# TG21_Slave_Device_Led.net
KiCad netlist of a schematic drawn in Altium Designer
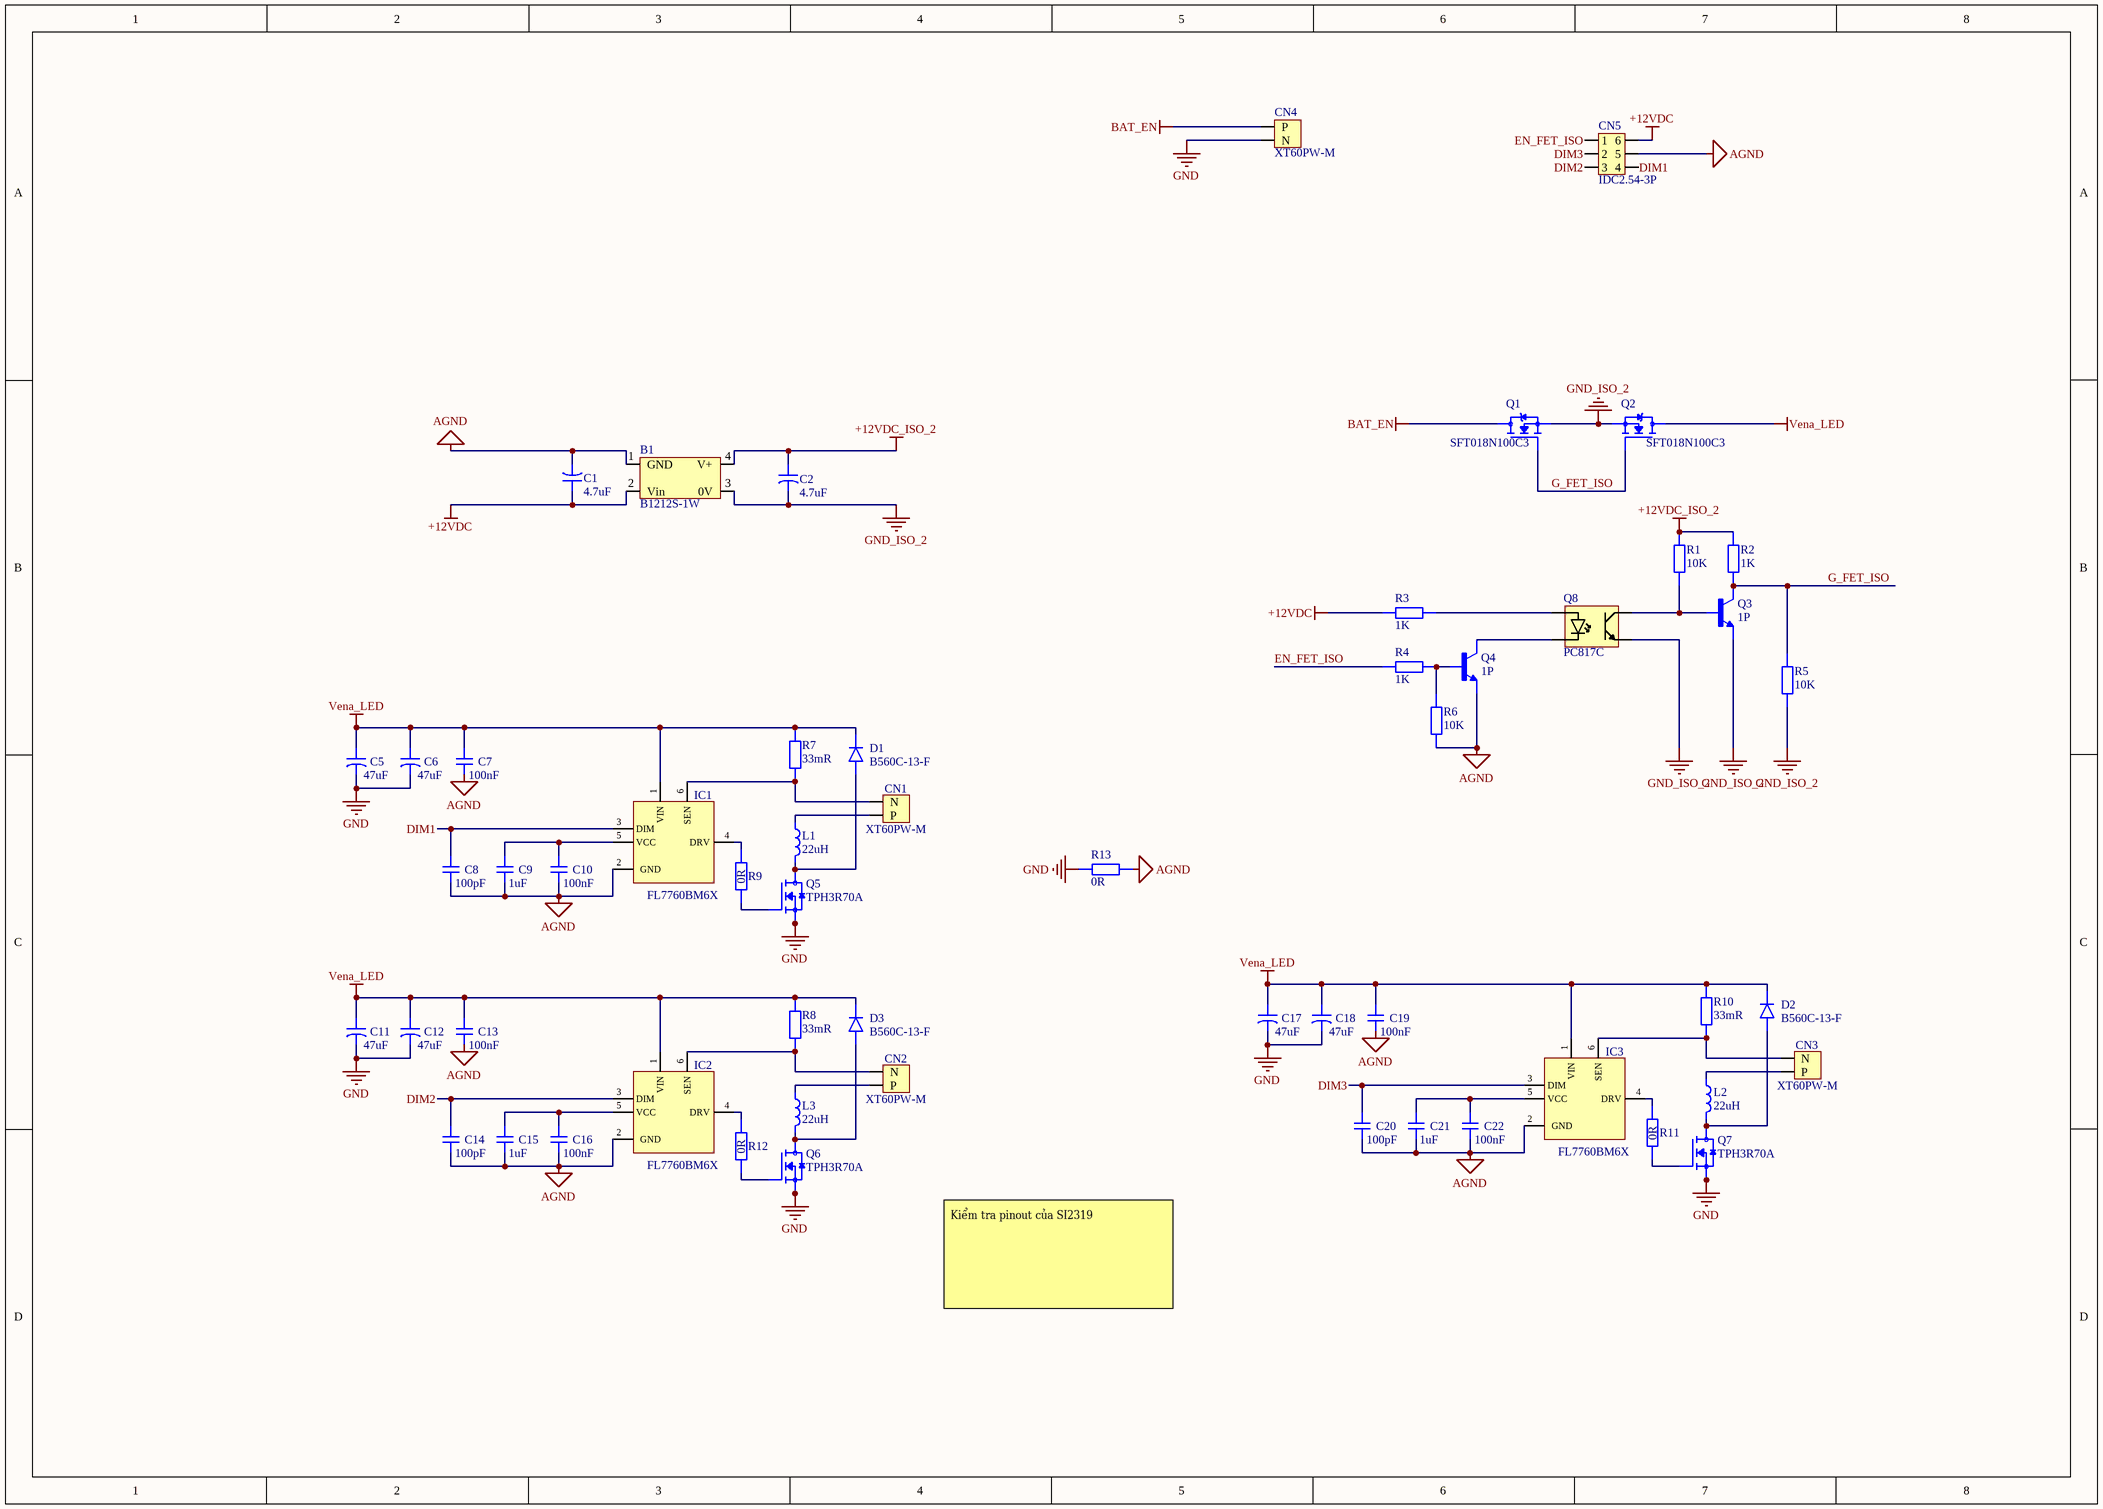
[diagram p0: TG21_Slave_Device_Led.SchDoc]

(export (version "E")
  (design (tool "Eeschema 10.0.6"))
  (components
    (comp (ref "B1")
      (value "B1212S-1W")
      (footprint "SIP-4")
      (description "Isolated Module DC DC Converter Buck 1 Output 12V 84mA 10.8V~13.2V Input")
      (fields (field (name "MANUFACTURER") "RLT") (field (name "LCSC PART #") "C512042"))
      (libsource (lib "TG21_Slave_Device_Led_1") (part "B1212-1W"))
    )
    (comp (ref "C1")
      (value "4.7uF")
      (footprint "PLUGIN,D5xL11mm")
      (description "4.7uF 50V Aluminum Electrolytic Capacitors Through Hole,D5xL11mm 5000hrs@105℃")
      (fields (field (name "MANUFACTURER") "Rubycon") (field (name "MFR.PART #") "50YXF4R7MEFC5X11"))
      (libsource (lib "CbyP") (part "50YXF4R7MEFC5X11"))
    )
    (comp (ref "C2")
      (value "4.7uF")
      (footprint "PLUGIN,D5xL11mm")
      (description "4.7uF 50V Aluminum Electrolytic Capacitors Through Hole,D5xL11mm 5000hrs@105℃")
      (fields (field (name "MANUFACTURER") "Rubycon") (field (name "MFR.PART #") "50YXF4R7MEFC5X11"))
      (libsource (lib "CbyP") (part "50YXF4R7MEFC5X11"))
    )
    (comp (ref "C5")
      (value "47uF")
      (footprint "PLUGIN,D6.3xL12mm")
      (description "47uF 63V Aluminum Electrolytic Capacitors Through Hole,D6.3xL12mm 5000hrs@105℃")
      (fields (field (name "MANUFACTURER") "AISHI") (field (name "MFR.PART #") "ERS1JM470E12OT"))
      (libsource (lib "CbyP") (part "ERS1JM470E12OT"))
    )
    (comp (ref "C6")
      (value "47uF")
      (footprint "PLUGIN,D6.3xL12mm")
      (description "47uF 63V Aluminum Electrolytic Capacitors Through Hole,D6.3xL12mm 5000hrs@105℃")
      (fields (field (name "MANUFACTURER") "AISHI") (field (name "MFR.PART #") "ERS1JM470E12OT"))
      (libsource (lib "CbyP") (part "ERS1JM470E12OT"))
    )
    (comp (ref "C7")
      (value "100nF")
      (footprint "CAP-0603")
      (description "100nF ±10% 50V Ceramic Capacitor X7R 0603")
      (fields (field (name "MANUFACTURER") "Samsung Electro-Mechanics") (field (name "LCSC PART #") "C1591"))
      (libsource (lib "CbyP") (part "CL10B104KB8NNNC"))
    )
    (comp (ref "C8")
      (value "100pF")
      (footprint "CAP-0603")
      (description "100pF ±5% 50V Ceramic Capacitor C0G 0603")
      (fields
        (field (name "MANUFACTURER") "Samsung Electro-Mechanics")
        (field (name "MFR.PART #") "CL10C101JB8NNNC")
      )
      (libsource (lib "CbyP") (part "CL10C101JB8NNNC"))
    )
    (comp (ref "C9")
      (value "1uF")
      (footprint "CAP-0603")
      (description "1uF ±10% 50V Ceramic Capacitor X7R 0603")
      (fields
        (field (name "MANUFACTURER") "Samsung Electro-Mechanics")
        (field (name "MFR.PART #") "CL10B105KB8NQNC")
      )
      (libsource (lib "CbyP") (part "CL10B105KB8NQNC"))
    )
    (comp (ref "C10")
      (value "100nF")
      (footprint "CAP-0603")
      (description "100nF ±10% 50V Ceramic Capacitor X7R 0603")
      (fields (field (name "MANUFACTURER") "Samsung Electro-Mechanics") (field (name "LCSC PART #") "C1591"))
      (libsource (lib "CbyP") (part "CL10B104KB8NNNC"))
    )
    (comp (ref "C11")
      (value "47uF")
      (footprint "PLUGIN,D6.3xL12mm")
      (description "47uF 63V Aluminum Electrolytic Capacitors Through Hole,D6.3xL12mm 5000hrs@105℃")
      (fields (field (name "MANUFACTURER") "AISHI") (field (name "MFR.PART #") "ERS1JM470E12OT"))
      (libsource (lib "CbyP") (part "ERS1JM470E12OT"))
    )
    (comp (ref "C12")
      (value "47uF")
      (footprint "PLUGIN,D6.3xL12mm")
      (description "47uF 63V Aluminum Electrolytic Capacitors Through Hole,D6.3xL12mm 5000hrs@105℃")
      (fields (field (name "MANUFACTURER") "AISHI") (field (name "MFR.PART #") "ERS1JM470E12OT"))
      (libsource (lib "CbyP") (part "ERS1JM470E12OT"))
    )
    (comp (ref "C13")
      (value "100nF")
      (footprint "CAP-0603")
      (description "100nF ±10% 50V Ceramic Capacitor X7R 0603")
      (fields (field (name "MANUFACTURER") "Samsung Electro-Mechanics") (field (name "LCSC PART #") "C1591"))
      (libsource (lib "CbyP") (part "CL10B104KB8NNNC"))
    )
    (comp (ref "C14")
      (value "100pF")
      (footprint "CAP-0603")
      (description "100pF ±5% 50V Ceramic Capacitor C0G 0603")
      (fields
        (field (name "MANUFACTURER") "Samsung Electro-Mechanics")
        (field (name "MFR.PART #") "CL10C101JB8NNNC")
      )
      (libsource (lib "CbyP") (part "CL10C101JB8NNNC"))
    )
    (comp (ref "C15")
      (value "1uF")
      (footprint "CAP-0603")
      (description "1uF ±10% 50V Ceramic Capacitor X7R 0603")
      (fields
        (field (name "MANUFACTURER") "Samsung Electro-Mechanics")
        (field (name "MFR.PART #") "CL10B105KB8NQNC")
      )
      (libsource (lib "CbyP") (part "CL10B105KB8NQNC"))
    )
    (comp (ref "C16")
      (value "100nF")
      (footprint "CAP-0603")
      (description "100nF ±10% 50V Ceramic Capacitor X7R 0603")
      (fields (field (name "MANUFACTURER") "Samsung Electro-Mechanics") (field (name "LCSC PART #") "C1591"))
      (libsource (lib "CbyP") (part "CL10B104KB8NNNC"))
    )
    (comp (ref "C17")
      (value "47uF")
      (footprint "PLUGIN,D6.3xL12mm")
      (description "47uF 63V Aluminum Electrolytic Capacitors Through Hole,D6.3xL12mm 5000hrs@105℃")
      (fields (field (name "MANUFACTURER") "AISHI") (field (name "MFR.PART #") "ERS1JM470E12OT"))
      (libsource (lib "CbyP") (part "ERS1JM470E12OT"))
    )
    (comp (ref "C18")
      (value "47uF")
      (footprint "PLUGIN,D6.3xL12mm")
      (description "47uF 63V Aluminum Electrolytic Capacitors Through Hole,D6.3xL12mm 5000hrs@105℃")
      (fields (field (name "MANUFACTURER") "AISHI") (field (name "MFR.PART #") "ERS1JM470E12OT"))
      (libsource (lib "CbyP") (part "ERS1JM470E12OT"))
    )
    (comp (ref "C19")
      (value "100nF")
      (footprint "CAP-0603")
      (description "100nF ±10% 50V Ceramic Capacitor X7R 0603")
      (fields (field (name "MANUFACTURER") "Samsung Electro-Mechanics") (field (name "LCSC PART #") "C1591"))
      (libsource (lib "CbyP") (part "CL10B104KB8NNNC"))
    )
    (comp (ref "C20")
      (value "100pF")
      (footprint "CAP-0603")
      (description "100pF ±5% 50V Ceramic Capacitor C0G 0603")
      (fields
        (field (name "MANUFACTURER") "Samsung Electro-Mechanics")
        (field (name "MFR.PART #") "CL10C101JB8NNNC")
      )
      (libsource (lib "CbyP") (part "CL10C101JB8NNNC"))
    )
    (comp (ref "C21")
      (value "1uF")
      (footprint "CAP-0603")
      (description "1uF ±10% 50V Ceramic Capacitor X7R 0603")
      (fields
        (field (name "MANUFACTURER") "Samsung Electro-Mechanics")
        (field (name "MFR.PART #") "CL10B105KB8NQNC")
      )
      (libsource (lib "CbyP") (part "CL10B105KB8NQNC"))
    )
    (comp (ref "C22")
      (value "100nF")
      (footprint "CAP-0603")
      (description "100nF ±10% 50V Ceramic Capacitor X7R 0603")
      (fields (field (name "MANUFACTURER") "Samsung Electro-Mechanics") (field (name "LCSC PART #") "C1591"))
      (libsource (lib "CbyP") (part "CL10B104KB8NNNC"))
    )
    (comp (ref "CN1")
      (value "XT60PW-M")
      (footprint "XT60PW-M")
      (description "Banana and Tip Connector Adapters RoHS")
      (fields (field (name "MANUFACTURER") "Changzhou Amass Elec") (field (name "LCSC PART #") "C98732"))
      (libsource (lib "CbyP") (part "XT60PW-M"))
    )
    (comp (ref "CN2")
      (value "XT60PW-M")
      (footprint "XT60PW-M")
      (description "Banana and Tip Connector Adapters RoHS")
      (fields (field (name "MANUFACTURER") "Changzhou Amass Elec") (field (name "LCSC PART #") "C98732"))
      (libsource (lib "CbyP") (part "XT60PW-M"))
    )
    (comp (ref "CN3")
      (value "XT60PW-M")
      (footprint "XT60PW-M")
      (description "Banana and Tip Connector Adapters RoHS")
      (fields (field (name "MANUFACTURER") "Changzhou Amass Elec") (field (name "LCSC PART #") "C98732"))
      (libsource (lib "CbyP") (part "XT60PW-M"))
    )
    (comp (ref "CN4")
      (value "XT60PW-M")
      (footprint "XT60PW-M")
      (description "Banana and Tip Connector Adapters RoHS")
      (fields (field (name "MANUFACTURER") "Changzhou Amass Elec") (field (name "LCSC PART #") "C98732"))
      (libsource (lib "") (part "XT60PW-M_1"))
    )
    (comp (ref "CN5")
      (value "IDC2.54-3P")
      (footprint "IDC Through Hole,Right Angle,P=2.54mm, 2x3P")
      (description "Connector IDC Header Through Hole, Right Angle 6 position 2.54mm")
      (fields
        (field (name "MANUFACTURER") "BOOMELE(Boom Precision Elec)")
        (field (name "MFR.PART #") "2.54-2*3P")
      )
      (libsource (lib "CbyP") (part "2.54-2*3P"))
    )
    (comp (ref "D1")
      (value "B560C-13-F")
      (footprint "SMC")
      (description "100A 1 Independent 60V 700mV@5A 5A SMC(DO-214AB) Single Diodes RoHS")
      (fields (field (name "MANUFACTURER") "DIODES") (field (name "LCSC PART #") "C85100"))
      (libsource (lib "CbyP") (part "B560C-13-F"))
    )
    (comp (ref "D2")
      (value "B560C-13-F")
      (footprint "SMC")
      (description "100A 1 Independent 60V 700mV@5A 5A SMC(DO-214AB) Single Diodes RoHS")
      (fields (field (name "MANUFACTURER") "DIODES") (field (name "LCSC PART #") "C85100"))
      (libsource (lib "CbyP") (part "B560C-13-F"))
    )
    (comp (ref "D3")
      (value "B560C-13-F")
      (footprint "SMC")
      (description "100A 1 Independent 60V 700mV@5A 5A SMC(DO-214AB) Single Diodes RoHS")
      (fields (field (name "MANUFACTURER") "DIODES") (field (name "LCSC PART #") "C85100"))
      (libsource (lib "CbyP") (part "B560C-13-F"))
    )
    (comp (ref "IC1")
      (value "FL7760BM6X")
      (footprint "SOT23-6")
      (description "High-Side Sensing Constant Current Buck Controller for High Switching Frequency LED Driver")
      (fields (field (name "MANUFACTURER") "onsemi") (field (name "LCSC PART #") "C367388"))
      (libsource (lib "CbyP") (part "FL7760BM6X"))
    )
    (comp (ref "IC2")
      (value "FL7760BM6X")
      (footprint "SOT23-6")
      (description "High-Side Sensing Constant Current Buck Controller for High Switching Frequency LED Driver")
      (fields (field (name "MANUFACTURER") "onsemi") (field (name "LCSC PART #") "C367388"))
      (libsource (lib "CbyP") (part "FL7760BM6X"))
    )
    (comp (ref "IC3")
      (value "FL7760BM6X")
      (footprint "SOT23-6")
      (description "High-Side Sensing Constant Current Buck Controller for High Switching Frequency LED Driver")
      (fields (field (name "MANUFACTURER") "onsemi") (field (name "LCSC PART #") "C367388"))
      (libsource (lib "CbyP") (part "FL7760BM6X"))
    )
    (comp (ref "L1")
      (value "22uH")
      (footprint "SMD,11x10mm")
      (description "8A 22uH 35mΩ 10A Molded Inductor ±20% SMD,11x10mm Fixed Inductors RoHS")
      (fields (field (name "MANUFACTURER") "PROD Tech") (field (name "MFR.PART #") "PSPMAA1082T-220M-CGP"))
      (libsource (lib "CbyP") (part "PSPMAA1082T-220M-CGP"))
    )
    (comp (ref "L2")
      (value "22uH")
      (footprint "SMD,11x10mm")
      (description "8A 22uH 35mΩ 10A Molded Inductor ±20% SMD,11x10mm Fixed Inductors RoHS")
      (fields (field (name "MANUFACTURER") "PROD Tech") (field (name "MFR.PART #") "PSPMAA1082T-220M-CGP"))
      (libsource (lib "CbyP") (part "PSPMAA1082T-220M-CGP"))
    )
    (comp (ref "L3")
      (value "22uH")
      (footprint "SMD,11x10mm")
      (description "8A 22uH 35mΩ 10A Molded Inductor ±20% SMD,11x10mm Fixed Inductors RoHS")
      (fields (field (name "MANUFACTURER") "PROD Tech") (field (name "MFR.PART #") "PSPMAA1082T-220M-CGP"))
      (libsource (lib "CbyP") (part "PSPMAA1082T-220M-CGP"))
    )
    (comp (ref "Q1")
      (value "SFT018N100C3")
      (footprint "TOLL")
      (description "N-Channel 100V 320A 312W Surface Mount TOLL")
      (fields (field (name "MANUFACTURER") "SCILICON") (field (name "LCSC PART #") "C42395330"))
      (libsource (lib "CbyP") (part "SFT018N100C3"))
    )
    (comp (ref "Q2")
      (value "SFT018N100C3")
      (footprint "TOLL")
      (description "N-Channel 100V 320A 312W Surface Mount TOLL")
      (fields (field (name "MANUFACTURER") "SCILICON") (field (name "LCSC PART #") "C42395330"))
      (libsource (lib "CbyP") (part "SFT018N100C3"))
    )
    (comp (ref "Q3")
      (value "1P")
      (footprint "SOT-23")
      (description "Bipolar (BJT) Transistor NPN 40V 600mA 225mW Surface Mount SOT-23")
      (fields (field (name "MANUFACTURER") "onsemi") (field (name "MFR.PART #") "MMBT2222ALT1G"))
      (libsource (lib "CbyP") (part "MMBT2222ALT1G"))
    )
    (comp (ref "Q4")
      (value "1P")
      (footprint "SOT-23")
      (description "Bipolar (BJT) Transistor NPN 40V 600mA 225mW Surface Mount SOT-23")
      (fields (field (name "MANUFACTURER") "onsemi") (field (name "MFR.PART #") "MMBT2222ALT1G"))
      (libsource (lib "CbyP") (part "MMBT2222ALT1G"))
    )
    (comp (ref "Q5")
      (value "TPH3R70A")
      (footprint "PDFN5060-8L-1.1MM")
      (description "N-Channel 100V 90A 170W SOP-8-Advance")
      (fields (field (name "MANUFACTURER") "TOSHIBA") (field (name "MFR.PART #") "TPH3R70APL,L1Q(M"))
      (libsource (lib "CbyP") (part "TPH3R70APL,L1Q(M"))
    )
    (comp (ref "Q6")
      (value "TPH3R70A")
      (footprint "PDFN5060-8L-1.1MM")
      (description "N-Channel 100V 90A 170W SOP-8-Advance")
      (fields (field (name "MANUFACTURER") "TOSHIBA") (field (name "MFR.PART #") "TPH3R70APL,L1Q(M"))
      (libsource (lib "CbyP") (part "TPH3R70APL,L1Q(M"))
    )
    (comp (ref "Q7")
      (value "TPH3R70A")
      (footprint "PDFN5060-8L-1.1MM")
      (description "N-Channel 100V 90A 170W SOP-8-Advance")
      (fields (field (name "MANUFACTURER") "TOSHIBA") (field (name "MFR.PART #") "TPH3R70APL,L1Q(M"))
      (libsource (lib "CbyP") (part "TPH3R70APL,L1Q(M"))
    )
    (comp (ref "Q8")
      (value "PC817C")
      (footprint "SOP-4")
      (description "Phototransistor Output 5kVrms 1 Channel SMD-4P")
      (fields (field (name "MANUFACTURER") "HXY MOSFET") (field (name "LCSC PART #") "C5451663"))
      (libsource (lib "CbyP") (part "HXY MOSFET PC817C"))
    )
    (comp (ref "R1")
      (value "10K")
      (footprint "RES-0603")
      (description "100mW 10kΩ 75V Thick Film Resistor ±100ppm/℃ ±1% 0603 Chip Resistor - Surface Mount RoHS")
      (fields (field (name "MANUFACTURER") "YAGEO") (field (name "LCSC PART #") "C98220"))
      (libsource (lib "CbyP") (part "RC0603FR-0710KL"))
    )
    (comp (ref "R2")
      (value "1K")
      (footprint "RES-0603")
      (description "100mW 1kΩ 75V Thick Film Resistor ±100ppm/℃ ±1% 0603 Chip Resistor - Surface Mount RoHS")
      (fields (field (name "MANUFACTURER") "YAGEO") (field (name "MFR.PART #") "RC0603FR-071KL"))
      (libsource (lib "CbyP") (part "RC0603FR-071KL"))
    )
    (comp (ref "R3")
      (value "1K")
      (footprint "RES-0603")
      (description "100mW 1kΩ 75V Thick Film Resistor ±100ppm/℃ ±1% 0603 Chip Resistor - Surface Mount RoHS")
      (fields (field (name "MANUFACTURER") "YAGEO") (field (name "MFR.PART #") "RC0603FR-071KL"))
      (libsource (lib "CbyP") (part "RC0603FR-071KL"))
    )
    (comp (ref "R4")
      (value "1K")
      (footprint "RES-0603")
      (description "100mW 1kΩ 75V Thick Film Resistor ±100ppm/℃ ±1% 0603 Chip Resistor - Surface Mount RoHS")
      (fields (field (name "MANUFACTURER") "YAGEO") (field (name "MFR.PART #") "RC0603FR-071KL"))
      (libsource (lib "CbyP") (part "RC0603FR-071KL"))
    )
    (comp (ref "R5")
      (value "10K")
      (footprint "RES-0603")
      (description "100mW 10kΩ 75V Thick Film Resistor ±100ppm/℃ ±1% 0603 Chip Resistor - Surface Mount RoHS")
      (fields (field (name "MANUFACTURER") "YAGEO") (field (name "LCSC PART #") "C98220"))
      (libsource (lib "CbyP") (part "RC0603FR-0710KL"))
    )
    (comp (ref "R6")
      (value "10K")
      (footprint "RES-0603")
      (description "100mW 10kΩ 75V Thick Film Resistor ±100ppm/℃ ±1% 0603 Chip Resistor - Surface Mount RoHS")
      (fields (field (name "MANUFACTURER") "YAGEO") (field (name "LCSC PART #") "C98220"))
      (libsource (lib "CbyP") (part "RC0603FR-0710KL"))
    )
    (comp (ref "R7")
      (value "33mR")
      (footprint "RES-2512")
      (description "33mΩ 3W Current Sense Resistor ±1% ±50ppm/℃ 2512 Chip Resistor - Surface Mount RoHS")
      (fields (field (name "MANUFACTURER") "Milliohm") (field (name "MFR.PART #") "HoLLR2512-3W-33mR-1%"))
      (libsource (lib "CbyP") (part "HoLLR2512-3W-33mR-1%"))
    )
    (comp (ref "R8")
      (value "33mR")
      (footprint "RES-2512")
      (description "33mΩ 3W Current Sense Resistor ±1% ±50ppm/℃ 2512 Chip Resistor - Surface Mount RoHS")
      (fields (field (name "MANUFACTURER") "Milliohm") (field (name "MFR.PART #") "HoLLR2512-3W-33mR-1%"))
      (libsource (lib "CbyP") (part "HoLLR2512-3W-33mR-1%"))
    )
    (comp (ref "R9")
      (value "0R")
      (footprint "RES-0603")
      (description "0Ω 100mW 75V Thick Film Resistor ±1% 0603 Chip Resistor - Surface Mount RoHS")
      (fields (field (name "MFR.PART #") "RC0603FR-070RL") (field (name "MANUFACTURER") "YAGEO"))
      (libsource (lib "CbyP") (part "RC0603FR-070RL"))
    )
    (comp (ref "R10")
      (value "33mR")
      (footprint "RES-2512")
      (description "33mΩ 3W Current Sense Resistor ±1% ±50ppm/℃ 2512 Chip Resistor - Surface Mount RoHS")
      (fields (field (name "MANUFACTURER") "Milliohm") (field (name "MFR.PART #") "HoLLR2512-3W-33mR-1%"))
      (libsource (lib "CbyP") (part "HoLLR2512-3W-33mR-1%"))
    )
    (comp (ref "R11")
      (value "0R")
      (footprint "RES-0603")
      (description "0Ω 100mW 75V Thick Film Resistor ±1% 0603 Chip Resistor - Surface Mount RoHS")
      (fields (field (name "MFR.PART #") "RC0603FR-070RL") (field (name "MANUFACTURER") "YAGEO"))
      (libsource (lib "CbyP") (part "RC0603FR-070RL"))
    )
    (comp (ref "R12")
      (value "0R")
      (footprint "RES-0603")
      (description "0Ω 100mW 75V Thick Film Resistor ±1% 0603 Chip Resistor - Surface Mount RoHS")
      (fields (field (name "MFR.PART #") "RC0603FR-070RL") (field (name "MANUFACTURER") "YAGEO"))
      (libsource (lib "CbyP") (part "RC0603FR-070RL"))
    )
    (comp (ref "R13")
      (value "0R")
      (footprint "RES-0603")
      (description "0Ω 100mW 75V Thick Film Resistor ±1% 0603 Chip Resistor - Surface Mount RoHS")
      (fields (field (name "MFR.PART #") "RC0603FR-070RL") (field (name "MANUFACTURER") "YAGEO"))
      (libsource (lib "CbyP") (part "RC0603FR-070RL"))
    )
  )
  (nets
    (net (code "1") (name "+12VDC") (class "Default")
      (node (ref "B1") (pin "2") (pinfunction "Vin_2") (pintype "passive"))
      (node (ref "C1") (pin "1") (pinfunction "1_1") (pintype "passive"))
      (node (ref "CN5") (pin "6") (pinfunction "6_6") (pintype "passive"))
      (node (ref "R3") (pin "1") (pinfunction "1_1") (pintype "passive"))
    )
    (net (code "2") (name "+12VDC_ISO_2") (class "Default")
      (node (ref "B1") (pin "4") (pinfunction "V+_4") (pintype "passive"))
      (node (ref "C2") (pin "1") (pinfunction "1_1") (pintype "passive"))
      (node (ref "R1") (pin "2") (pinfunction "2_2") (pintype "passive"))
      (node (ref "R2") (pin "2") (pinfunction "2_2") (pintype "passive"))
    )
    (net (code "3") (name "/DIM1") (class "Default")
      (node (ref "C8") (pin "1") (pinfunction "1_1") (pintype "passive"))
      (node (ref "CN5") (pin "4") (pinfunction "4_4") (pintype "passive"))
      (node (ref "IC1") (pin "3") (pinfunction "DIM_3") (pintype "passive"))
    )
    (net (code "4") (name "/DIM2") (class "Default")
      (node (ref "C14") (pin "1") (pinfunction "1_1") (pintype "passive"))
      (node (ref "CN5") (pin "3") (pinfunction "3_3") (pintype "passive"))
      (node (ref "IC2") (pin "3") (pinfunction "DIM_3") (pintype "passive"))
    )
    (net (code "5") (name "/DIM3") (class "Default")
      (node (ref "C20") (pin "1") (pinfunction "1_1") (pintype "passive"))
      (node (ref "CN5") (pin "2") (pinfunction "2_2") (pintype "passive"))
      (node (ref "IC3") (pin "3") (pinfunction "DIM_3") (pintype "passive"))
    )
    (net (code "6") (name "/EN_FET_ISO") (class "Default")
      (node (ref "CN5") (pin "1") (pinfunction "1_1") (pintype "passive"))
      (node (ref "R4") (pin "1") (pinfunction "1_1") (pintype "passive"))
    )
    (net (code "7") (name "/G_FET_ISO") (class "Default")
      (node (ref "Q1") (pin "1") (pinfunction "G_1") (pintype "passive"))
      (node (ref "Q2") (pin "1") (pinfunction "G_1") (pintype "passive"))
      (node (ref "Q3") (pin "3") (pinfunction "C_3") (pintype "passive"))
      (node (ref "R2") (pin "1") (pinfunction "1_1") (pintype "passive"))
      (node (ref "R5") (pin "2") (pinfunction "2_2") (pintype "passive"))
    )
    (net (code "8") (name "AGND") (class "Default")
      (node (ref "B1") (pin "1") (pinfunction "GND_1") (pintype "passive"))
      (node (ref "C1") (pin "2") (pinfunction "2_2") (pintype "passive"))
      (node (ref "C10") (pin "2") (pinfunction "2_2") (pintype "passive"))
      (node (ref "C13") (pin "2") (pinfunction "2_2") (pintype "passive"))
      (node (ref "C14") (pin "2") (pinfunction "2_2") (pintype "passive"))
      (node (ref "C15") (pin "2") (pinfunction "2_2") (pintype "passive"))
      (node (ref "C16") (pin "2") (pinfunction "2_2") (pintype "passive"))
      (node (ref "C19") (pin "2") (pinfunction "2_2") (pintype "passive"))
      (node (ref "C20") (pin "2") (pinfunction "2_2") (pintype "passive"))
      (node (ref "C21") (pin "2") (pinfunction "2_2") (pintype "passive"))
      (node (ref "C22") (pin "2") (pinfunction "2_2") (pintype "passive"))
      (node (ref "C7") (pin "2") (pinfunction "2_2") (pintype "passive"))
      (node (ref "C8") (pin "2") (pinfunction "2_2") (pintype "passive"))
      (node (ref "C9") (pin "2") (pinfunction "2_2") (pintype "passive"))
      (node (ref "CN5") (pin "5") (pinfunction "5_5") (pintype "passive"))
      (node (ref "IC1") (pin "2") (pinfunction "GND_2") (pintype "passive"))
      (node (ref "IC2") (pin "2") (pinfunction "GND_2") (pintype "passive"))
      (node (ref "IC3") (pin "2") (pinfunction "GND_2") (pintype "passive"))
      (node (ref "Q4") (pin "2") (pinfunction "E_2") (pintype "passive"))
      (node (ref "R13") (pin "2") (pinfunction "2_2") (pintype "passive"))
      (node (ref "R6") (pin "1") (pinfunction "1_1") (pintype "passive"))
    )
    (net (code "9") (name "BAT_EN") (class "Default")
      (node (ref "CN4") (pin "1") (pinfunction "P_1") (pintype "passive"))
      (node (ref "Q1") (pin "3") (pinfunction "D_3") (pintype "passive"))
    )
    (net (code "10") (name "GND") (class "Default")
      (node (ref "C11") (pin "2") (pinfunction "2_2") (pintype "passive"))
      (node (ref "C12") (pin "2") (pinfunction "2_2") (pintype "passive"))
      (node (ref "C17") (pin "2") (pinfunction "2_2") (pintype "passive"))
      (node (ref "C18") (pin "2") (pinfunction "2_2") (pintype "passive"))
      (node (ref "C5") (pin "2") (pinfunction "2_2") (pintype "passive"))
      (node (ref "C6") (pin "2") (pinfunction "2_2") (pintype "passive"))
      (node (ref "CN4") (pin "2") (pinfunction "N_2") (pintype "passive"))
      (node (ref "Q5") (pin "1") (pinfunction "S_1") (pintype "passive"))
      (node (ref "Q5") (pin "2") (pinfunction "S_2") (pintype "passive"))
      (node (ref "Q5") (pin "3") (pinfunction "S_3") (pintype "passive"))
      (node (ref "Q6") (pin "1") (pinfunction "S_1") (pintype "passive"))
      (node (ref "Q6") (pin "2") (pinfunction "S_2") (pintype "passive"))
      (node (ref "Q6") (pin "3") (pinfunction "S_3") (pintype "passive"))
      (node (ref "Q7") (pin "1") (pinfunction "S_1") (pintype "passive"))
      (node (ref "Q7") (pin "2") (pinfunction "S_2") (pintype "passive"))
      (node (ref "Q7") (pin "3") (pinfunction "S_3") (pintype "passive"))
      (node (ref "R13") (pin "1") (pinfunction "1_1") (pintype "passive"))
    )
    (net (code "11") (name "GND_ISO_2") (class "Default")
      (node (ref "B1") (pin "3") (pinfunction "0V_3") (pintype "passive"))
      (node (ref "C2") (pin "2") (pinfunction "2_2") (pintype "passive"))
      (node (ref "Q1") (pin "2") (pinfunction "S_2") (pintype "passive"))
      (node (ref "Q2") (pin "2") (pinfunction "S_2") (pintype "passive"))
      (node (ref "Q3") (pin "2") (pinfunction "E_2") (pintype "passive"))
      (node (ref "Q8") (pin "3") (pinfunction "E_3") (pintype "passive"))
      (node (ref "R5") (pin "1") (pinfunction "1_1") (pintype "passive"))
    )
    (net (code "12") (name "Net-(CN1-N)") (class "Default")
      (node (ref "CN1") (pin "2") (pinfunction "N_2") (pintype "passive"))
      (node (ref "IC1") (pin "6") (pinfunction "SEN_6") (pintype "passive"))
      (node (ref "R7") (pin "1") (pinfunction "1_1") (pintype "passive"))
    )
    (net (code "13") (name "Net-(CN1-P)") (class "Default")
      (node (ref "CN1") (pin "1") (pinfunction "P_1") (pintype "passive"))
      (node (ref "L1") (pin "1") (pinfunction "1_1") (pintype "passive"))
    )
    (net (code "14") (name "Net-(CN2-N)") (class "Default")
      (node (ref "CN2") (pin "2") (pinfunction "N_2") (pintype "passive"))
      (node (ref "IC2") (pin "6") (pinfunction "SEN_6") (pintype "passive"))
      (node (ref "R8") (pin "1") (pinfunction "1_1") (pintype "passive"))
    )
    (net (code "15") (name "Net-(CN2-P)") (class "Default")
      (node (ref "CN2") (pin "1") (pinfunction "P_1") (pintype "passive"))
      (node (ref "L3") (pin "1") (pinfunction "1_1") (pintype "passive"))
    )
    (net (code "16") (name "Net-(CN3-N)") (class "Default")
      (node (ref "CN3") (pin "2") (pinfunction "N_2") (pintype "passive"))
      (node (ref "IC3") (pin "6") (pinfunction "SEN_6") (pintype "passive"))
      (node (ref "R10") (pin "1") (pinfunction "1_1") (pintype "passive"))
    )
    (net (code "17") (name "Net-(CN3-P)") (class "Default")
      (node (ref "CN3") (pin "1") (pinfunction "P_1") (pintype "passive"))
      (node (ref "L2") (pin "1") (pinfunction "1_1") (pintype "passive"))
    )
    (net (code "18") (name "Net-(D1-A)") (class "Default")
      (node (ref "D1") (pin "1") (pinfunction "A_1") (pintype "passive"))
      (node (ref "L1") (pin "2") (pinfunction "2_2") (pintype "passive"))
      (node (ref "Q5") (pin "5_8") (pinfunction "D_5_8") (pintype "passive"))
    )
    (net (code "19") (name "Net-(D2-A)") (class "Default")
      (node (ref "D2") (pin "1") (pinfunction "A_1") (pintype "passive"))
      (node (ref "L2") (pin "2") (pinfunction "2_2") (pintype "passive"))
      (node (ref "Q7") (pin "5_8") (pinfunction "D_5_8") (pintype "passive"))
    )
    (net (code "20") (name "Net-(D3-A)") (class "Default")
      (node (ref "D3") (pin "1") (pinfunction "A_1") (pintype "passive"))
      (node (ref "L3") (pin "2") (pinfunction "2_2") (pintype "passive"))
      (node (ref "Q6") (pin "5_8") (pinfunction "D_5_8") (pintype "passive"))
    )
    (net (code "21") (name "Net-(IC1-DRV)") (class "Default")
      (node (ref "IC1") (pin "4") (pinfunction "DRV_4") (pintype "passive"))
      (node (ref "R9") (pin "2") (pinfunction "2_2") (pintype "passive"))
    )
    (net (code "22") (name "Net-(IC1-VCC)") (class "Default")
      (node (ref "C10") (pin "1") (pinfunction "1_1") (pintype "passive"))
      (node (ref "C9") (pin "1") (pinfunction "1_1") (pintype "passive"))
      (node (ref "IC1") (pin "5") (pinfunction "VCC_5") (pintype "passive"))
    )
    (net (code "23") (name "Net-(IC2-DRV)") (class "Default")
      (node (ref "IC2") (pin "4") (pinfunction "DRV_4") (pintype "passive"))
      (node (ref "R12") (pin "2") (pinfunction "2_2") (pintype "passive"))
    )
    (net (code "24") (name "Net-(IC2-VCC)") (class "Default")
      (node (ref "C15") (pin "1") (pinfunction "1_1") (pintype "passive"))
      (node (ref "C16") (pin "1") (pinfunction "1_1") (pintype "passive"))
      (node (ref "IC2") (pin "5") (pinfunction "VCC_5") (pintype "passive"))
    )
    (net (code "25") (name "Net-(IC3-DRV)") (class "Default")
      (node (ref "IC3") (pin "4") (pinfunction "DRV_4") (pintype "passive"))
      (node (ref "R11") (pin "2") (pinfunction "2_2") (pintype "passive"))
    )
    (net (code "26") (name "Net-(IC3-VCC)") (class "Default")
      (node (ref "C21") (pin "1") (pinfunction "1_1") (pintype "passive"))
      (node (ref "C22") (pin "1") (pinfunction "1_1") (pintype "passive"))
      (node (ref "IC3") (pin "5") (pinfunction "VCC_5") (pintype "passive"))
    )
    (net (code "27") (name "Net-(Q3-B)") (class "Default")
      (node (ref "Q3") (pin "1") (pinfunction "B_1") (pintype "passive"))
      (node (ref "Q8") (pin "4") (pinfunction "C_4") (pintype "passive"))
      (node (ref "R1") (pin "1") (pinfunction "1_1") (pintype "passive"))
    )
    (net (code "28") (name "Net-(Q4-B)") (class "Default")
      (node (ref "Q4") (pin "1") (pinfunction "B_1") (pintype "passive"))
      (node (ref "R4") (pin "2") (pinfunction "2_2") (pintype "passive"))
      (node (ref "R6") (pin "2") (pinfunction "2_2") (pintype "passive"))
    )
    (net (code "29") (name "Net-(Q4-C)") (class "Default")
      (node (ref "Q4") (pin "3") (pinfunction "C_3") (pintype "passive"))
      (node (ref "Q8") (pin "2") (pinfunction "K_2") (pintype "passive"))
    )
    (net (code "30") (name "Net-(Q5-G)") (class "Default")
      (node (ref "Q5") (pin "4") (pinfunction "G_4") (pintype "passive"))
      (node (ref "R9") (pin "1") (pinfunction "1_1") (pintype "passive"))
    )
    (net (code "31") (name "Net-(Q6-G)") (class "Default")
      (node (ref "Q6") (pin "4") (pinfunction "G_4") (pintype "passive"))
      (node (ref "R12") (pin "1") (pinfunction "1_1") (pintype "passive"))
    )
    (net (code "32") (name "Net-(Q7-G)") (class "Default")
      (node (ref "Q7") (pin "4") (pinfunction "G_4") (pintype "passive"))
      (node (ref "R11") (pin "1") (pinfunction "1_1") (pintype "passive"))
    )
    (net (code "33") (name "Net-(Q8-A)") (class "Default")
      (node (ref "Q8") (pin "1") (pinfunction "A_1") (pintype "passive"))
      (node (ref "R3") (pin "2") (pinfunction "2_2") (pintype "passive"))
    )
    (net (code "34") (name "Vena_LED") (class "Default")
      (node (ref "C11") (pin "1") (pinfunction "1_1") (pintype "passive"))
      (node (ref "C12") (pin "1") (pinfunction "1_1") (pintype "passive"))
      (node (ref "C13") (pin "1") (pinfunction "1_1") (pintype "passive"))
      (node (ref "C17") (pin "1") (pinfunction "1_1") (pintype "passive"))
      (node (ref "C18") (pin "1") (pinfunction "1_1") (pintype "passive"))
      (node (ref "C19") (pin "1") (pinfunction "1_1") (pintype "passive"))
      (node (ref "C5") (pin "1") (pinfunction "1_1") (pintype "passive"))
      (node (ref "C6") (pin "1") (pinfunction "1_1") (pintype "passive"))
      (node (ref "C7") (pin "1") (pinfunction "1_1") (pintype "passive"))
      (node (ref "D1") (pin "2") (pinfunction "K_2") (pintype "passive"))
      (node (ref "D2") (pin "2") (pinfunction "K_2") (pintype "passive"))
      (node (ref "D3") (pin "2") (pinfunction "K_2") (pintype "passive"))
      (node (ref "IC1") (pin "1") (pinfunction "VIN_1") (pintype "passive"))
      (node (ref "IC2") (pin "1") (pinfunction "VIN_1") (pintype "passive"))
      (node (ref "IC3") (pin "1") (pinfunction "VIN_1") (pintype "passive"))
      (node (ref "Q2") (pin "3") (pinfunction "D_3") (pintype "passive"))
      (node (ref "R10") (pin "2") (pinfunction "2_2") (pintype "passive"))
      (node (ref "R7") (pin "2") (pinfunction "2_2") (pintype "passive"))
      (node (ref "R8") (pin "2") (pinfunction "2_2") (pintype "passive"))
    )
  )
)
